# DSKY_keyboard.net
KiCad netlist of a schematic drawn in Altium Designer
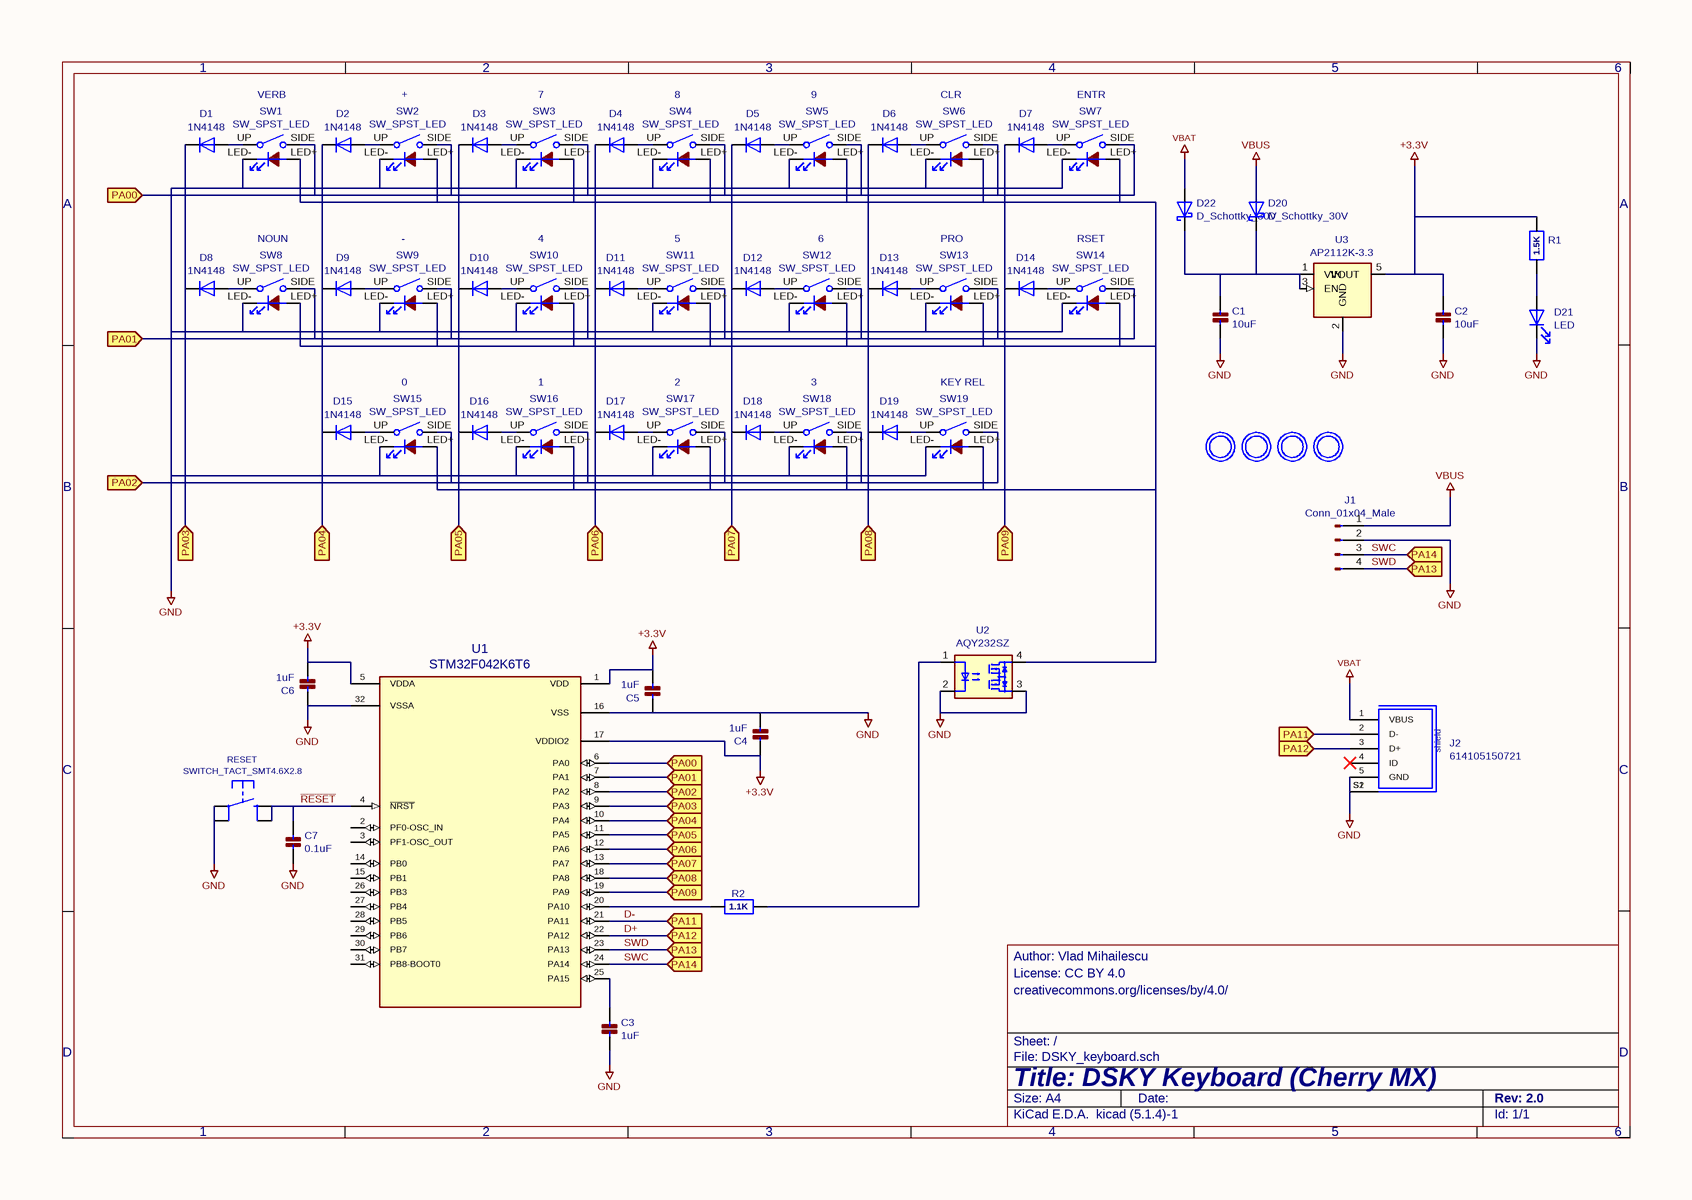
[diagram p0: DSKY_keyboard.SchDoc]

(export (version "E")
  (design (tool "Eeschema 10.0.6"))
  (components
    (comp (ref "C1") (value "10uF") (libsource (lib "") (part "CAP_CERAMIC0805-NOOUTLINE_1")))
    (comp (ref "C2") (value "10uF") (libsource (lib "") (part "CAP_CERAMIC0805-NOOUTLINE_1")))
    (comp (ref "C3") (value "1uF") (libsource (lib "") (part "CAP_CERAMIC0805-NOOUTLINE_1")))
    (comp (ref "C4") (value "1uF") (libsource (lib "eagle-import") (part "CAP_CERAMIC0805-NOOUTLINE")))
    (comp (ref "C5") (value "1uF") (libsource (lib "eagle-import") (part "CAP_CERAMIC0805-NOOUTLINE")))
    (comp (ref "C6") (value "1uF") (libsource (lib "eagle-import") (part "CAP_CERAMIC0805-NOOUTLINE")))
    (comp (ref "C7") (value "0.1uF") (libsource (lib "") (part "CAP_CERAMIC0805-NOOUTLINE_1")))
    (comp (ref "D1") (value "1N4148") (libsource (lib "Diode") (part "1N4148")))
    (comp (ref "D2") (value "1N4148") (libsource (lib "Diode") (part "1N4148")))
    (comp (ref "D3") (value "1N4148") (libsource (lib "Diode") (part "1N4148")))
    (comp (ref "D4") (value "1N4148") (libsource (lib "Diode") (part "1N4148")))
    (comp (ref "D5") (value "1N4148") (libsource (lib "Diode") (part "1N4148")))
    (comp (ref "D6") (value "1N4148") (libsource (lib "Diode") (part "1N4148")))
    (comp (ref "D7") (value "1N4148") (libsource (lib "Diode") (part "1N4148")))
    (comp (ref "D8") (value "1N4148") (libsource (lib "Diode") (part "1N4148")))
    (comp (ref "D9") (value "1N4148") (libsource (lib "Diode") (part "1N4148")))
    (comp (ref "D10") (value "1N4148") (libsource (lib "Diode") (part "1N4148")))
    (comp (ref "D11") (value "1N4148") (libsource (lib "Diode") (part "1N4148")))
    (comp (ref "D12") (value "1N4148") (libsource (lib "Diode") (part "1N4148")))
    (comp (ref "D13") (value "1N4148") (libsource (lib "Diode") (part "1N4148")))
    (comp (ref "D14") (value "1N4148") (libsource (lib "Diode") (part "1N4148")))
    (comp (ref "D15") (value "1N4148") (libsource (lib "Diode") (part "1N4148")))
    (comp (ref "D16") (value "1N4148") (libsource (lib "Diode") (part "1N4148")))
    (comp (ref "D17") (value "1N4148") (libsource (lib "Diode") (part "1N4148")))
    (comp (ref "D18") (value "1N4148") (libsource (lib "Diode") (part "1N4148")))
    (comp (ref "D19") (value "1N4148") (libsource (lib "Diode") (part "1N4148")))
    (comp (ref "D20") (value "D_Schottky_30V") (libsource (lib "Device") (part "D_Schottky")))
    (comp (ref "D21") (value "LED") (libsource (lib "Device") (part "LED")))
    (comp (ref "D22") (value "D_Schottky_30V") (libsource (lib "Device") (part "D_Schottky")))
    (comp (ref "J1") (value "Conn_01x04_Male") (libsource (lib "Connector") (part "Conn_01x04_Male")))
    (comp (ref "J2") (value "614105150721") (libsource (lib "614105150721") (part "614105150721")))
    (comp (ref "J3") (value "MOUNTINGHOLE3.0") (libsource (lib "eagle-import") (part "MOUNTINGHOLE3.0")))
    (comp (ref "J4") (value "MOUNTINGHOLE3.0") (libsource (lib "eagle-import") (part "MOUNTINGHOLE3.0")))
    (comp (ref "J5") (value "MOUNTINGHOLE3.0") (libsource (lib "eagle-import") (part "MOUNTINGHOLE3.0")))
    (comp (ref "J6") (value "MOUNTINGHOLE3.0") (libsource (lib "eagle-import") (part "MOUNTINGHOLE3.0")))
    (comp (ref "R1") (value "1.5K") (libsource (lib "eagle-import") (part "RESISTOR_0603_NOOUT")))
    (comp (ref "R2") (value "1.1K") (libsource (lib "eagle-import") (part "RESISTOR_0603_NOOUT")))
    (comp (ref "RESET")
      (value "SWITCH_TACT_SMT4.6X2.8")
      (libsource (lib "eagle-import") (part "SWITCH_TACT_SMT4.6X2.8"))
    )
    (comp (ref "SW1") (value "SW_SPST_LED") (libsource (lib "Switch") (part "SW_GATERON_LED")))
    (comp (ref "SW2") (value "SW_SPST_LED") (libsource (lib "Switch") (part "SW_GATERON_LED")))
    (comp (ref "SW3") (value "SW_SPST_LED") (libsource (lib "Switch") (part "SW_GATERON_LED")))
    (comp (ref "SW4") (value "SW_SPST_LED") (libsource (lib "Switch") (part "SW_GATERON_LED")))
    (comp (ref "SW5") (value "SW_SPST_LED") (libsource (lib "Switch") (part "SW_GATERON_LED")))
    (comp (ref "SW6") (value "SW_SPST_LED") (libsource (lib "Switch") (part "SW_GATERON_LED")))
    (comp (ref "SW7") (value "SW_SPST_LED") (libsource (lib "Switch") (part "SW_GATERON_LED")))
    (comp (ref "SW8") (value "SW_SPST_LED") (libsource (lib "Switch") (part "SW_GATERON_LED")))
    (comp (ref "SW9") (value "SW_SPST_LED") (libsource (lib "Switch") (part "SW_GATERON_LED")))
    (comp (ref "SW10") (value "SW_SPST_LED") (libsource (lib "Switch") (part "SW_GATERON_LED")))
    (comp (ref "SW11") (value "SW_SPST_LED") (libsource (lib "Switch") (part "SW_GATERON_LED")))
    (comp (ref "SW12") (value "SW_SPST_LED") (libsource (lib "Switch") (part "SW_GATERON_LED")))
    (comp (ref "SW13") (value "SW_SPST_LED") (libsource (lib "Switch") (part "SW_GATERON_LED")))
    (comp (ref "SW14") (value "SW_SPST_LED") (libsource (lib "Switch") (part "SW_GATERON_LED")))
    (comp (ref "SW15") (value "SW_SPST_LED") (libsource (lib "Switch") (part "SW_GATERON_LED")))
    (comp (ref "SW16") (value "SW_SPST_LED") (libsource (lib "Switch") (part "SW_GATERON_LED")))
    (comp (ref "SW17") (value "SW_SPST_LED") (libsource (lib "Switch") (part "SW_GATERON_LED")))
    (comp (ref "SW18") (value "SW_SPST_LED") (libsource (lib "Switch") (part "SW_GATERON_LED")))
    (comp (ref "SW19") (value "SW_SPST_LED") (libsource (lib "Switch") (part "SW_GATERON_LED")))
    (comp (ref "U1") (value "STM32F042K6T6") (libsource (lib "STM32F042K6T6") (part "STM32F042K6T6")))
    (comp (ref "U2") (value "AQY232SZ") (libsource (lib "eagle-import") (part "AQY232SZ")))
    (comp (ref "U3") (value "AP2112K-3.3") (libsource (lib "Regulator_Linear") (part "AP2112K-3.3")))
  )
  (nets
    (net (code "1") (name "+3.3V") (class "Default")
      (node (ref "C2") (pin "1") (pinfunction "1_1") (pintype "passive"))
      (node (ref "C4") (pin "1") (pinfunction "1_1") (pintype "passive"))
      (node (ref "C5") (pin "2") (pinfunction "2_2") (pintype "passive"))
      (node (ref "C6") (pin "2") (pinfunction "2_2") (pintype "passive"))
      (node (ref "R1") (pin "1") (pinfunction "1_1") (pintype "passive"))
      (node (ref "U1") (pin "1") (pinfunction "VDD_1") (pintype "power_in"))
      (node (ref "U1") (pin "17") (pinfunction "VDDIO2_17") (pintype "power_in"))
      (node (ref "U1") (pin "5") (pinfunction "VDDA_5") (pintype "power_in"))
      (node (ref "U3") (pin "5") (pinfunction "VOUT_5") (pintype "power_in"))
    )
    (net (code "2") (name "/D+") (class "Default")
      (node (ref "J2") (pin "3") (pinfunction "D+_3") (pintype "passive"))
      (node (ref "U1") (pin "22") (pinfunction "PA12_22") (pintype "bidirectional"))
    )
    (net (code "3") (name "/D-") (class "Default")
      (node (ref "J2") (pin "2") (pinfunction "D-_2") (pintype "passive"))
      (node (ref "U1") (pin "21") (pinfunction "PA11_21") (pintype "bidirectional"))
    )
    (net (code "4") (name "/PA00") (class "Default")
      (node (ref "SW1") (pin "SIDE") (pinfunction "SIDE_SIDE") (pintype "passive"))
      (node (ref "SW2") (pin "SIDE") (pinfunction "SIDE_SIDE") (pintype "passive"))
      (node (ref "SW3") (pin "SIDE") (pinfunction "SIDE_SIDE") (pintype "passive"))
      (node (ref "SW4") (pin "SIDE") (pinfunction "SIDE_SIDE") (pintype "passive"))
      (node (ref "SW5") (pin "SIDE") (pinfunction "SIDE_SIDE") (pintype "passive"))
      (node (ref "SW6") (pin "SIDE") (pinfunction "SIDE_SIDE") (pintype "passive"))
      (node (ref "SW7") (pin "SIDE") (pinfunction "SIDE_SIDE") (pintype "passive"))
      (node (ref "U1") (pin "6") (pinfunction "PA0_6") (pintype "bidirectional"))
    )
    (net (code "5") (name "/PA01") (class "Default")
      (node (ref "SW10") (pin "SIDE") (pinfunction "SIDE_SIDE") (pintype "passive"))
      (node (ref "SW11") (pin "SIDE") (pinfunction "SIDE_SIDE") (pintype "passive"))
      (node (ref "SW12") (pin "SIDE") (pinfunction "SIDE_SIDE") (pintype "passive"))
      (node (ref "SW13") (pin "SIDE") (pinfunction "SIDE_SIDE") (pintype "passive"))
      (node (ref "SW14") (pin "SIDE") (pinfunction "SIDE_SIDE") (pintype "passive"))
      (node (ref "SW8") (pin "SIDE") (pinfunction "SIDE_SIDE") (pintype "passive"))
      (node (ref "SW9") (pin "SIDE") (pinfunction "SIDE_SIDE") (pintype "passive"))
      (node (ref "U1") (pin "7") (pinfunction "PA1_7") (pintype "bidirectional"))
    )
    (net (code "6") (name "/PA02") (class "Default")
      (node (ref "SW15") (pin "SIDE") (pinfunction "SIDE_SIDE") (pintype "passive"))
      (node (ref "SW16") (pin "SIDE") (pinfunction "SIDE_SIDE") (pintype "passive"))
      (node (ref "SW17") (pin "SIDE") (pinfunction "SIDE_SIDE") (pintype "passive"))
      (node (ref "SW18") (pin "SIDE") (pinfunction "SIDE_SIDE") (pintype "passive"))
      (node (ref "SW19") (pin "SIDE") (pinfunction "SIDE_SIDE") (pintype "passive"))
      (node (ref "U1") (pin "8") (pinfunction "PA2_8") (pintype "bidirectional"))
    )
    (net (code "7") (name "/PA03") (class "Default")
      (node (ref "D1") (pin "1") (pinfunction "K_1") (pintype "passive"))
      (node (ref "D8") (pin "1") (pinfunction "K_1") (pintype "passive"))
      (node (ref "U1") (pin "9") (pinfunction "PA3_9") (pintype "bidirectional"))
    )
    (net (code "8") (name "/PA04") (class "Default")
      (node (ref "D15") (pin "1") (pinfunction "K_1") (pintype "passive"))
      (node (ref "D2") (pin "1") (pinfunction "K_1") (pintype "passive"))
      (node (ref "D9") (pin "1") (pinfunction "K_1") (pintype "passive"))
      (node (ref "U1") (pin "10") (pinfunction "PA4_10") (pintype "bidirectional"))
    )
    (net (code "9") (name "/PA05") (class "Default")
      (node (ref "D10") (pin "1") (pinfunction "K_1") (pintype "passive"))
      (node (ref "D16") (pin "1") (pinfunction "K_1") (pintype "passive"))
      (node (ref "D3") (pin "1") (pinfunction "K_1") (pintype "passive"))
      (node (ref "U1") (pin "11") (pinfunction "PA5_11") (pintype "bidirectional"))
    )
    (net (code "10") (name "/PA06") (class "Default")
      (node (ref "D11") (pin "1") (pinfunction "K_1") (pintype "passive"))
      (node (ref "D17") (pin "1") (pinfunction "K_1") (pintype "passive"))
      (node (ref "D4") (pin "1") (pinfunction "K_1") (pintype "passive"))
      (node (ref "U1") (pin "12") (pinfunction "PA6_12") (pintype "bidirectional"))
    )
    (net (code "11") (name "/PA07") (class "Default")
      (node (ref "D12") (pin "1") (pinfunction "K_1") (pintype "passive"))
      (node (ref "D18") (pin "1") (pinfunction "K_1") (pintype "passive"))
      (node (ref "D5") (pin "1") (pinfunction "K_1") (pintype "passive"))
      (node (ref "U1") (pin "13") (pinfunction "PA7_13") (pintype "bidirectional"))
    )
    (net (code "12") (name "/PA08") (class "Default")
      (node (ref "D13") (pin "1") (pinfunction "K_1") (pintype "passive"))
      (node (ref "D19") (pin "1") (pinfunction "K_1") (pintype "passive"))
      (node (ref "D6") (pin "1") (pinfunction "K_1") (pintype "passive"))
      (node (ref "U1") (pin "18") (pinfunction "PA8_18") (pintype "bidirectional"))
    )
    (net (code "13") (name "/PA09") (class "Default")
      (node (ref "D14") (pin "1") (pinfunction "K_1") (pintype "passive"))
      (node (ref "D7") (pin "1") (pinfunction "K_1") (pintype "passive"))
      (node (ref "U1") (pin "19") (pinfunction "PA9_19") (pintype "bidirectional"))
    )
    (net (code "14") (name "/SWC") (class "Default")
      (node (ref "J1") (pin "3") (pinfunction "Pin_3_3") (pintype "passive"))
      (node (ref "U1") (pin "24") (pinfunction "PA14_24") (pintype "bidirectional"))
    )
    (net (code "15") (name "/SWD") (class "Default")
      (node (ref "J1") (pin "4") (pinfunction "Pin_4_4") (pintype "passive"))
      (node (ref "U1") (pin "23") (pinfunction "PA13_23") (pintype "bidirectional"))
    )
    (net (code "16") (name "/~{RESET}") (class "Default")
      (node (ref "C7") (pin "1") (pinfunction "1_1") (pintype "passive"))
      (node (ref "RESET") (pin "B") (pinfunction "S_B") (pintype "passive"))
      (node (ref "RESET") (pin "B'") (pinfunction "S1_B'") (pintype "passive"))
      (node (ref "U1") (pin "4") (pinfunction "~{NRST}_4") (pintype "input"))
    )
    (net (code "17") (name "GND") (class "Default")
      (node (ref "C1") (pin "2") (pinfunction "2_2") (pintype "passive"))
      (node (ref "C2") (pin "2") (pinfunction "2_2") (pintype "passive"))
      (node (ref "C3") (pin "2") (pinfunction "2_2") (pintype "passive"))
      (node (ref "C4") (pin "2") (pinfunction "2_2") (pintype "passive"))
      (node (ref "C5") (pin "1") (pinfunction "1_1") (pintype "passive"))
      (node (ref "C6") (pin "1") (pinfunction "1_1") (pintype "passive"))
      (node (ref "C7") (pin "2") (pinfunction "2_2") (pintype "passive"))
      (node (ref "D21") (pin "1") (pinfunction "K_1") (pintype "passive"))
      (node (ref "J1") (pin "2") (pinfunction "Pin_2_2") (pintype "passive"))
      (node (ref "J2") (pin "5") (pinfunction "GND_5") (pintype "passive"))
      (node (ref "J2") (pin "S1") (pinfunction "S1_S1") (pintype "passive"))
      (node (ref "J2") (pin "S2") (pinfunction "S2_S2") (pintype "passive"))
      (node (ref "RESET") (pin "A") (pinfunction "P_A") (pintype "passive"))
      (node (ref "RESET") (pin "A'") (pinfunction "P1_A'") (pintype "passive"))
      (node (ref "SW1") (pin "LED-") (pinfunction "LED-_LED-") (pintype "passive"))
      (node (ref "SW10") (pin "LED-") (pinfunction "LED-_LED-") (pintype "passive"))
      (node (ref "SW11") (pin "LED-") (pinfunction "LED-_LED-") (pintype "passive"))
      (node (ref "SW12") (pin "LED-") (pinfunction "LED-_LED-") (pintype "passive"))
      (node (ref "SW13") (pin "LED-") (pinfunction "LED-_LED-") (pintype "passive"))
      (node (ref "SW14") (pin "LED-") (pinfunction "LED-_LED-") (pintype "passive"))
      (node (ref "SW15") (pin "LED-") (pinfunction "LED-_LED-") (pintype "passive"))
      (node (ref "SW16") (pin "LED-") (pinfunction "LED-_LED-") (pintype "passive"))
      (node (ref "SW17") (pin "LED-") (pinfunction "LED-_LED-") (pintype "passive"))
      (node (ref "SW18") (pin "LED-") (pinfunction "LED-_LED-") (pintype "passive"))
      (node (ref "SW19") (pin "LED-") (pinfunction "LED-_LED-") (pintype "passive"))
      (node (ref "SW2") (pin "LED-") (pinfunction "LED-_LED-") (pintype "passive"))
      (node (ref "SW3") (pin "LED-") (pinfunction "LED-_LED-") (pintype "passive"))
      (node (ref "SW4") (pin "LED-") (pinfunction "LED-_LED-") (pintype "passive"))
      (node (ref "SW5") (pin "LED-") (pinfunction "LED-_LED-") (pintype "passive"))
      (node (ref "SW6") (pin "LED-") (pinfunction "LED-_LED-") (pintype "passive"))
      (node (ref "SW7") (pin "LED-") (pinfunction "LED-_LED-") (pintype "passive"))
      (node (ref "SW8") (pin "LED-") (pinfunction "LED-_LED-") (pintype "passive"))
      (node (ref "SW9") (pin "LED-") (pinfunction "LED-_LED-") (pintype "passive"))
      (node (ref "U1") (pin "16") (pinfunction "VSS_16") (pintype "power_in"))
      (node (ref "U1") (pin "32") (pinfunction "VSSA_32") (pintype "power_in"))
      (node (ref "U2") (pin "2") (pinfunction "2_2") (pintype "passive"))
      (node (ref "U2") (pin "3") (pinfunction "3_3") (pintype "passive"))
      (node (ref "U3") (pin "2") (pinfunction "GND_2") (pintype "power_in"))
    )
    (net (code "18") (name "Net-(D1-A)") (class "Default")
      (node (ref "D1") (pin "2") (pinfunction "A_2") (pintype "passive"))
      (node (ref "SW1") (pin "UP") (pinfunction "UP_UP") (pintype "passive"))
    )
    (net (code "19") (name "Net-(D2-A)") (class "Default")
      (node (ref "D2") (pin "2") (pinfunction "A_2") (pintype "passive"))
      (node (ref "SW2") (pin "UP") (pinfunction "UP_UP") (pintype "passive"))
    )
    (net (code "20") (name "Net-(D3-A)") (class "Default")
      (node (ref "D3") (pin "2") (pinfunction "A_2") (pintype "passive"))
      (node (ref "SW3") (pin "UP") (pinfunction "UP_UP") (pintype "passive"))
    )
    (net (code "21") (name "Net-(D4-A)") (class "Default")
      (node (ref "D4") (pin "2") (pinfunction "A_2") (pintype "passive"))
      (node (ref "SW4") (pin "UP") (pinfunction "UP_UP") (pintype "passive"))
    )
    (net (code "22") (name "Net-(D5-A)") (class "Default")
      (node (ref "D5") (pin "2") (pinfunction "A_2") (pintype "passive"))
      (node (ref "SW5") (pin "UP") (pinfunction "UP_UP") (pintype "passive"))
    )
    (net (code "23") (name "Net-(D6-A)") (class "Default")
      (node (ref "D6") (pin "2") (pinfunction "A_2") (pintype "passive"))
      (node (ref "SW6") (pin "UP") (pinfunction "UP_UP") (pintype "passive"))
    )
    (net (code "24") (name "Net-(D7-A)") (class "Default")
      (node (ref "D7") (pin "2") (pinfunction "A_2") (pintype "passive"))
      (node (ref "SW7") (pin "UP") (pinfunction "UP_UP") (pintype "passive"))
    )
    (net (code "25") (name "Net-(D8-A)") (class "Default")
      (node (ref "D8") (pin "2") (pinfunction "A_2") (pintype "passive"))
      (node (ref "SW8") (pin "UP") (pinfunction "UP_UP") (pintype "passive"))
    )
    (net (code "26") (name "Net-(D9-A)") (class "Default")
      (node (ref "D9") (pin "2") (pinfunction "A_2") (pintype "passive"))
      (node (ref "SW9") (pin "UP") (pinfunction "UP_UP") (pintype "passive"))
    )
    (net (code "27") (name "Net-(D10-A)") (class "Default")
      (node (ref "D10") (pin "2") (pinfunction "A_2") (pintype "passive"))
      (node (ref "SW10") (pin "UP") (pinfunction "UP_UP") (pintype "passive"))
    )
    (net (code "28") (name "Net-(D11-A)") (class "Default")
      (node (ref "D11") (pin "2") (pinfunction "A_2") (pintype "passive"))
      (node (ref "SW11") (pin "UP") (pinfunction "UP_UP") (pintype "passive"))
    )
    (net (code "29") (name "Net-(D12-A)") (class "Default")
      (node (ref "D12") (pin "2") (pinfunction "A_2") (pintype "passive"))
      (node (ref "SW12") (pin "UP") (pinfunction "UP_UP") (pintype "passive"))
    )
    (net (code "30") (name "Net-(D13-A)") (class "Default")
      (node (ref "D13") (pin "2") (pinfunction "A_2") (pintype "passive"))
      (node (ref "SW13") (pin "UP") (pinfunction "UP_UP") (pintype "passive"))
    )
    (net (code "31") (name "Net-(D14-A)") (class "Default")
      (node (ref "D14") (pin "2") (pinfunction "A_2") (pintype "passive"))
      (node (ref "SW14") (pin "UP") (pinfunction "UP_UP") (pintype "passive"))
    )
    (net (code "32") (name "Net-(D15-A)") (class "Default")
      (node (ref "D15") (pin "2") (pinfunction "A_2") (pintype "passive"))
      (node (ref "SW15") (pin "UP") (pinfunction "UP_UP") (pintype "passive"))
    )
    (net (code "33") (name "Net-(D16-A)") (class "Default")
      (node (ref "D16") (pin "2") (pinfunction "A_2") (pintype "passive"))
      (node (ref "SW16") (pin "UP") (pinfunction "UP_UP") (pintype "passive"))
    )
    (net (code "34") (name "Net-(D17-A)") (class "Default")
      (node (ref "D17") (pin "2") (pinfunction "A_2") (pintype "passive"))
      (node (ref "SW17") (pin "UP") (pinfunction "UP_UP") (pintype "passive"))
    )
    (net (code "35") (name "Net-(D18-A)") (class "Default")
      (node (ref "D18") (pin "2") (pinfunction "A_2") (pintype "passive"))
      (node (ref "SW18") (pin "UP") (pinfunction "UP_UP") (pintype "passive"))
    )
    (net (code "36") (name "Net-(D19-A)") (class "Default")
      (node (ref "D19") (pin "2") (pinfunction "A_2") (pintype "passive"))
      (node (ref "SW19") (pin "UP") (pinfunction "UP_UP") (pintype "passive"))
    )
    (net (code "37") (name "Net-(D20-K)") (class "Default")
      (node (ref "C1") (pin "1") (pinfunction "1_1") (pintype "passive"))
      (node (ref "D20") (pin "1") (pinfunction "K_1") (pintype "passive"))
      (node (ref "D22") (pin "1") (pinfunction "K_1") (pintype "passive"))
      (node (ref "U3") (pin "1") (pinfunction "VIN_1") (pintype "power_in"))
      (node (ref "U3") (pin "3") (pinfunction "EN_3") (pintype "input"))
    )
    (net (code "38") (name "Net-(D21-A)") (class "Default")
      (node (ref "D21") (pin "2") (pinfunction "A_2") (pintype "passive"))
      (node (ref "R1") (pin "2") (pinfunction "2_2") (pintype "passive"))
    )
    (net (code "39") (name "Net-(R2-Pad1)") (class "Default")
      (node (ref "R2") (pin "1") (pinfunction "1_1") (pintype "passive"))
      (node (ref "U2") (pin "1") (pinfunction "1_1") (pintype "passive"))
    )
    (net (code "40") (name "Net-(SW1-PadLED+)") (class "Default")
      (node (ref "SW1") (pin "LED+") (pinfunction "LED+_LED+") (pintype "passive"))
      (node (ref "SW10") (pin "LED+") (pinfunction "LED+_LED+") (pintype "passive"))
      (node (ref "SW11") (pin "LED+") (pinfunction "LED+_LED+") (pintype "passive"))
      (node (ref "SW12") (pin "LED+") (pinfunction "LED+_LED+") (pintype "passive"))
      (node (ref "SW13") (pin "LED+") (pinfunction "LED+_LED+") (pintype "passive"))
      (node (ref "SW14") (pin "LED+") (pinfunction "LED+_LED+") (pintype "passive"))
      (node (ref "SW15") (pin "LED+") (pinfunction "LED+_LED+") (pintype "passive"))
      (node (ref "SW16") (pin "LED+") (pinfunction "LED+_LED+") (pintype "passive"))
      (node (ref "SW17") (pin "LED+") (pinfunction "LED+_LED+") (pintype "passive"))
      (node (ref "SW18") (pin "LED+") (pinfunction "LED+_LED+") (pintype "passive"))
      (node (ref "SW19") (pin "LED+") (pinfunction "LED+_LED+") (pintype "passive"))
      (node (ref "SW2") (pin "LED+") (pinfunction "LED+_LED+") (pintype "passive"))
      (node (ref "SW3") (pin "LED+") (pinfunction "LED+_LED+") (pintype "passive"))
      (node (ref "SW4") (pin "LED+") (pinfunction "LED+_LED+") (pintype "passive"))
      (node (ref "SW5") (pin "LED+") (pinfunction "LED+_LED+") (pintype "passive"))
      (node (ref "SW6") (pin "LED+") (pinfunction "LED+_LED+") (pintype "passive"))
      (node (ref "SW7") (pin "LED+") (pinfunction "LED+_LED+") (pintype "passive"))
      (node (ref "SW8") (pin "LED+") (pinfunction "LED+_LED+") (pintype "passive"))
      (node (ref "SW9") (pin "LED+") (pinfunction "LED+_LED+") (pintype "passive"))
      (node (ref "U2") (pin "4") (pinfunction "4_4") (pintype "passive"))
    )
    (net (code "41") (name "Net-(U1-PA10)") (class "Default")
      (node (ref "R2") (pin "2") (pinfunction "2_2") (pintype "passive"))
      (node (ref "U1") (pin "20") (pinfunction "PA10_20") (pintype "bidirectional"))
    )
    (net (code "42") (name "Net-(U1-PA15)") (class "Default")
      (node (ref "C3") (pin "1") (pinfunction "1_1") (pintype "passive"))
      (node (ref "U1") (pin "25") (pinfunction "PA15_25") (pintype "bidirectional"))
    )
    (net (code "43") (name "VBAT") (class "Default")
      (node (ref "D22") (pin "2") (pinfunction "A_2") (pintype "passive"))
      (node (ref "J2") (pin "1") (pinfunction "VBUS_1") (pintype "passive"))
    )
    (net (code "44") (name "VBUS") (class "Default")
      (node (ref "D20") (pin "2") (pinfunction "A_2") (pintype "passive"))
      (node (ref "J1") (pin "1") (pinfunction "Pin_1_1") (pintype "passive"))
    )
    (net (code "45") (name "unconnected-(J2-ID-Pad4)") (class "Default")
      (node (ref "J2") (pin "4") (pinfunction "ID_4") (pintype "passive+no_connect"))
    )
    (net (code "46") (name "unconnected-(U1-PB0-Pad14)") (class "Default")
      (node (ref "U1") (pin "14") (pinfunction "PB0_14") (pintype "bidirectional"))
    )
    (net (code "47") (name "unconnected-(U1-PB1-Pad15)") (class "Default")
      (node (ref "U1") (pin "15") (pinfunction "PB1_15") (pintype "bidirectional"))
    )
    (net (code "48") (name "unconnected-(U1-PB3-Pad26)") (class "Default")
      (node (ref "U1") (pin "26") (pinfunction "PB3_26") (pintype "bidirectional"))
    )
    (net (code "49") (name "unconnected-(U1-PB4-Pad27)") (class "Default")
      (node (ref "U1") (pin "27") (pinfunction "PB4_27") (pintype "bidirectional"))
    )
    (net (code "50") (name "unconnected-(U1-PB5-Pad28)") (class "Default")
      (node (ref "U1") (pin "28") (pinfunction "PB5_28") (pintype "bidirectional"))
    )
    (net (code "51") (name "unconnected-(U1-PB6-Pad29)") (class "Default")
      (node (ref "U1") (pin "29") (pinfunction "PB6_29") (pintype "bidirectional"))
    )
    (net (code "52") (name "unconnected-(U1-PB7-Pad30)") (class "Default")
      (node (ref "U1") (pin "30") (pinfunction "PB7_30") (pintype "bidirectional"))
    )
    (net (code "53") (name "unconnected-(U1-PB8-BOOT0-Pad31)") (class "Default")
      (node (ref "U1") (pin "31") (pinfunction "PB8-BOOT0_31") (pintype "bidirectional"))
    )
    (net (code "54") (name "unconnected-(U1-PF0-OSC_IN-Pad2)") (class "Default")
      (node (ref "U1") (pin "2") (pinfunction "PF0-OSC_IN_2") (pintype "bidirectional"))
    )
    (net (code "55") (name "unconnected-(U1-PF1-OSC_OUT-Pad3)") (class "Default")
      (node (ref "U1") (pin "3") (pinfunction "PF1-OSC_OUT_3") (pintype "bidirectional"))
    )
    (net (code "56") (name "unconnected-(U3-NC-Pad4)") (class "Default")
      (node (ref "U3") (pin "4") (pinfunction "NC_4") (pintype "passive"))
    )
  )
)
